# untitled.net
KiCad netlist of a schematic drawn in EAGLE
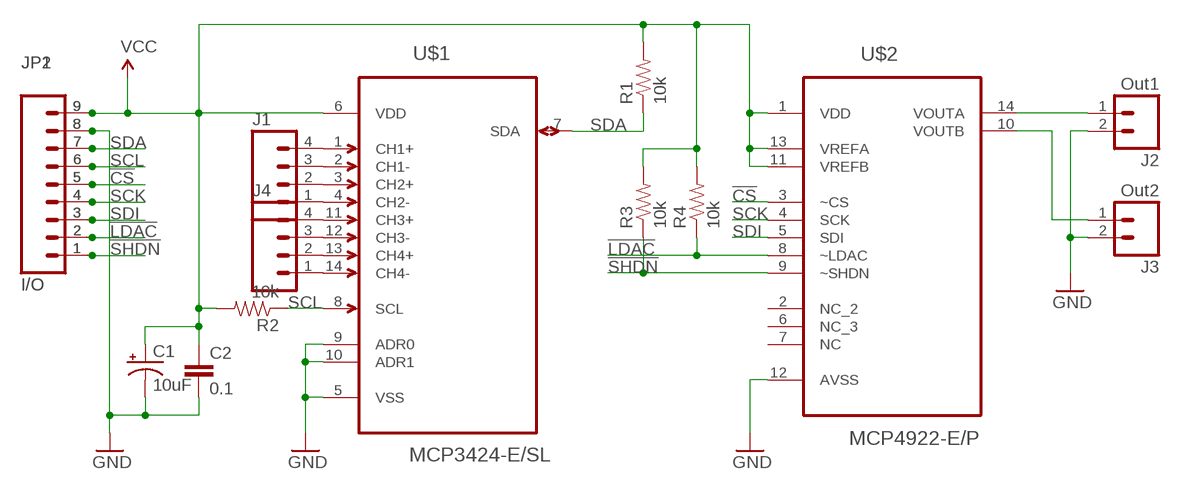
[diagram p0: schematic, sheet 1]

(export (version "E")
  (design (tool "Eeschema 10.0.6"))
  (components
    (comp (ref "C1")
      (value "10uF")
      (footprint "eagle-import:CPOL-RADIAL-10UF-25V")
      (libsource (lib "eagle-import") (part "CAP_POLPTH2"))
    )
    (comp (ref "C2")
      (value "0.1")
      (footprint "eagle-import:CAP-PTH-5MM")
      (libsource (lib "eagle-import") (part "CAPPTH1"))
    )
    (comp (ref "J1")
      (value "M04LONGPADS")
      (footprint "eagle-import:1X04_LONGPADS")
      (libsource (lib "eagle-import") (part "M04LONGPADS"))
    )
    (comp (ref "J2")
      (value "Out1")
      (footprint "eagle-import:1X02_LONGPADS")
      (libsource (lib "eagle-import") (part "M02PTH3"))
    )
    (comp (ref "J3")
      (value "Out2")
      (footprint "eagle-import:1X02_LONGPADS")
      (libsource (lib "eagle-import") (part "M02PTH3"))
    )
    (comp (ref "J4")
      (value "M04LONGPADS")
      (footprint "eagle-import:1X04_LONGPADS")
      (libsource (lib "eagle-import") (part "M04LONGPADS"))
    )
    (comp (ref "JP1")
      (value "I/O")
      (footprint "eagle-import:1X09_LONGPADS")
      (libsource (lib "eagle-import") (part "M09LONGPADS"))
    )
    (comp (ref "JP2")
      (value "I/O")
      (footprint "eagle-import:1X09_LONGPADS")
      (libsource (lib "eagle-import") (part "M09LONGPADS"))
    )
    (comp (ref "R1")
      (value "10k")
      (footprint "eagle-import:AXIAL-0.3")
      (libsource (lib "eagle-import") (part "RESISTORAXIAL-0.3"))
    )
    (comp (ref "R2")
      (value "10k")
      (footprint "eagle-import:AXIAL-0.3")
      (libsource (lib "eagle-import") (part "RESISTORAXIAL-0.3"))
    )
    (comp (ref "R3")
      (value "10k")
      (footprint "eagle-import:AXIAL-0.3")
      (libsource (lib "eagle-import") (part "RESISTORAXIAL-0.3"))
    )
    (comp (ref "R4")
      (value "10k")
      (footprint "eagle-import:AXIAL-0.3")
      (libsource (lib "eagle-import") (part "RESISTORAXIAL-0.3"))
    )
    (comp (ref "U$1")
      (value "MCP3424-E/SL")
      (footprint "eagle-import:SOIC127P600X175-14N")
      (libsource (lib "eagle-import") (part "MCP3424-E/SL"))
    )
    (comp (ref "U$2")
      (value "MCP4922-E/P")
      (footprint "eagle-import:DIP254P762X533-14")
      (libsource (lib "eagle-import") (part "MCP4922-E/P"))
    )
  )
  (nets
    (net (code "1") (name "/SCK") (class "Default")
      (node (ref "JP1") (pin "4") (pinfunction "4_4") (pintype "passive"))
      (node (ref "JP2") (pin "4") (pinfunction "4_4") (pintype "passive"))
      (node (ref "U$2") (pin "4") (pinfunction "SCK_4") (pintype "input"))
    )
    (net (code "2") (name "/SCL") (class "Default")
      (node (ref "JP1") (pin "6") (pinfunction "6_6") (pintype "passive"))
      (node (ref "JP2") (pin "6") (pinfunction "6_6") (pintype "passive"))
      (node (ref "R2") (pin "P$1") (pinfunction "1_P$1") (pintype "passive"))
      (node (ref "U$1") (pin "8") (pinfunction "SCL_8") (pintype "input"))
    )
    (net (code "3") (name "/SDA") (class "Default")
      (node (ref "JP1") (pin "7") (pinfunction "7_7") (pintype "passive"))
      (node (ref "JP2") (pin "7") (pinfunction "7_7") (pintype "passive"))
      (node (ref "R1") (pin "P$1") (pinfunction "1_P$1") (pintype "passive"))
      (node (ref "U$1") (pin "7") (pinfunction "SDA_7") (pintype "bidirectional"))
    )
    (net (code "4") (name "/SDI") (class "Default")
      (node (ref "JP1") (pin "3") (pinfunction "3_3") (pintype "passive"))
      (node (ref "JP2") (pin "3") (pinfunction "3_3") (pintype "passive"))
      (node (ref "U$2") (pin "5") (pinfunction "SDI_5") (pintype "input"))
    )
    (net (code "5") (name "/~{CS}") (class "Default")
      (node (ref "JP1") (pin "5") (pinfunction "5_5") (pintype "passive"))
      (node (ref "JP2") (pin "5") (pinfunction "5_5") (pintype "passive"))
      (node (ref "U$2") (pin "3") (pinfunction "~{CS}_3") (pintype "input"))
    )
    (net (code "6") (name "/~{LDAC}") (class "Default")
      (node (ref "JP1") (pin "2") (pinfunction "2_2") (pintype "passive"))
      (node (ref "JP2") (pin "2") (pinfunction "2_2") (pintype "passive"))
      (node (ref "R4") (pin "P$1") (pinfunction "1_P$1") (pintype "passive"))
      (node (ref "U$2") (pin "8") (pinfunction "~{LDAC}_8") (pintype "input"))
    )
    (net (code "7") (name "/~{SHDN}") (class "Default")
      (node (ref "JP1") (pin "1") (pinfunction "1_1") (pintype "passive"))
      (node (ref "JP2") (pin "1") (pinfunction "1_1") (pintype "passive"))
      (node (ref "R3") (pin "P$1") (pinfunction "1_P$1") (pintype "passive"))
      (node (ref "U$2") (pin "9") (pinfunction "~{SHDN}_9") (pintype "input"))
    )
    (net (code "8") (name "GND") (class "Default")
      (node (ref "C1") (pin "2") (pinfunction "-_2") (pintype "passive"))
      (node (ref "C2") (pin "2") (pinfunction "2_2") (pintype "passive"))
      (node (ref "J2") (pin "2") (pinfunction "2_2") (pintype "passive"))
      (node (ref "J3") (pin "2") (pinfunction "2_2") (pintype "passive"))
      (node (ref "JP1") (pin "8") (pinfunction "8_8") (pintype "passive"))
      (node (ref "JP2") (pin "8") (pinfunction "8_8") (pintype "passive"))
      (node (ref "U$1") (pin "10") (pinfunction "ADR1_10") (pintype "input"))
      (node (ref "U$1") (pin "5") (pinfunction "VSS_5") (pintype "power_in"))
      (node (ref "U$1") (pin "9") (pinfunction "ADR0_9") (pintype "input"))
      (node (ref "U$2") (pin "12") (pinfunction "AVSS_12") (pintype "power_in"))
    )
    (net (code "9") (name "Net-(U$1-CH1+)") (class "Default")
      (node (ref "J1") (pin "4") (pinfunction "4_4") (pintype "passive"))
      (node (ref "U$1") (pin "1") (pinfunction "CH1+_1") (pintype "input"))
    )
    (net (code "10") (name "Net-(U$1-CH1-)") (class "Default")
      (node (ref "J1") (pin "3") (pinfunction "3_3") (pintype "passive"))
      (node (ref "U$1") (pin "2") (pinfunction "CH1-_2") (pintype "input"))
    )
    (net (code "11") (name "Net-(U$1-CH2+)") (class "Default")
      (node (ref "J1") (pin "2") (pinfunction "2_2") (pintype "passive"))
      (node (ref "U$1") (pin "3") (pinfunction "CH2+_3") (pintype "input"))
    )
    (net (code "12") (name "Net-(U$1-CH2-)") (class "Default")
      (node (ref "J1") (pin "1") (pinfunction "1_1") (pintype "passive"))
      (node (ref "U$1") (pin "4") (pinfunction "CH2-_4") (pintype "input"))
    )
    (net (code "13") (name "Net-(U$1-CH3+)") (class "Default")
      (node (ref "J4") (pin "4") (pinfunction "4_4") (pintype "passive"))
      (node (ref "U$1") (pin "11") (pinfunction "CH3+_11") (pintype "input"))
    )
    (net (code "14") (name "Net-(U$1-CH3-)") (class "Default")
      (node (ref "J4") (pin "3") (pinfunction "3_3") (pintype "passive"))
      (node (ref "U$1") (pin "12") (pinfunction "CH3-_12") (pintype "input"))
    )
    (net (code "15") (name "Net-(U$1-CH4+)") (class "Default")
      (node (ref "J4") (pin "2") (pinfunction "2_2") (pintype "passive"))
      (node (ref "U$1") (pin "13") (pinfunction "CH4+_13") (pintype "input"))
    )
    (net (code "16") (name "Net-(U$1-CH4-)") (class "Default")
      (node (ref "J4") (pin "1") (pinfunction "1_1") (pintype "passive"))
      (node (ref "U$1") (pin "14") (pinfunction "CH4-_14") (pintype "input"))
    )
    (net (code "17") (name "Net-(U$2-VOUTA)") (class "Default")
      (node (ref "J2") (pin "1") (pinfunction "1_1") (pintype "passive"))
      (node (ref "U$2") (pin "14") (pinfunction "VOUTA_14") (pintype "output"))
    )
    (net (code "18") (name "Net-(U$2-VOUTB)") (class "Default")
      (node (ref "J3") (pin "1") (pinfunction "1_1") (pintype "passive"))
      (node (ref "U$2") (pin "10") (pinfunction "VOUTB_10") (pintype "output"))
    )
    (net (code "19") (name "VCC") (class "Default")
      (node (ref "C1") (pin "1") (pinfunction "+_1") (pintype "passive"))
      (node (ref "C2") (pin "1") (pinfunction "1_1") (pintype "passive"))
      (node (ref "JP1") (pin "9") (pinfunction "9_9") (pintype "passive"))
      (node (ref "JP2") (pin "9") (pinfunction "9_9") (pintype "passive"))
      (node (ref "R1") (pin "P$2") (pinfunction "2_P$2") (pintype "passive"))
      (node (ref "R2") (pin "P$2") (pinfunction "2_P$2") (pintype "passive"))
      (node (ref "R3") (pin "P$2") (pinfunction "2_P$2") (pintype "passive"))
      (node (ref "R4") (pin "P$2") (pinfunction "2_P$2") (pintype "passive"))
      (node (ref "U$1") (pin "6") (pinfunction "VDD_6") (pintype "power_in"))
      (node (ref "U$2") (pin "1") (pinfunction "VDD_1") (pintype "power_in"))
      (node (ref "U$2") (pin "11") (pinfunction "VREFB_11") (pintype "input"))
      (node (ref "U$2") (pin "13") (pinfunction "VREFA_13") (pintype "input"))
    )
    (net (code "20") (name "unconnected-(U$2-NC-Pad7)") (class "Default")
      (node (ref "U$2") (pin "7") (pinfunction "NC_7") (pintype "no_connect"))
    )
    (net (code "21") (name "unconnected-(U$2-NC_2-Pad2)") (class "Default")
      (node (ref "U$2") (pin "2") (pinfunction "NC_2_2") (pintype "no_connect"))
    )
    (net (code "22") (name "unconnected-(U$2-NC_3-Pad6)") (class "Default")
      (node (ref "U$2") (pin "6") (pinfunction "NC_3_6") (pintype "no_connect"))
    )
  )
)
